# SH9_-_MICROCONTROLLER.net
KiCad netlist of a schematic drawn in Altium Designer
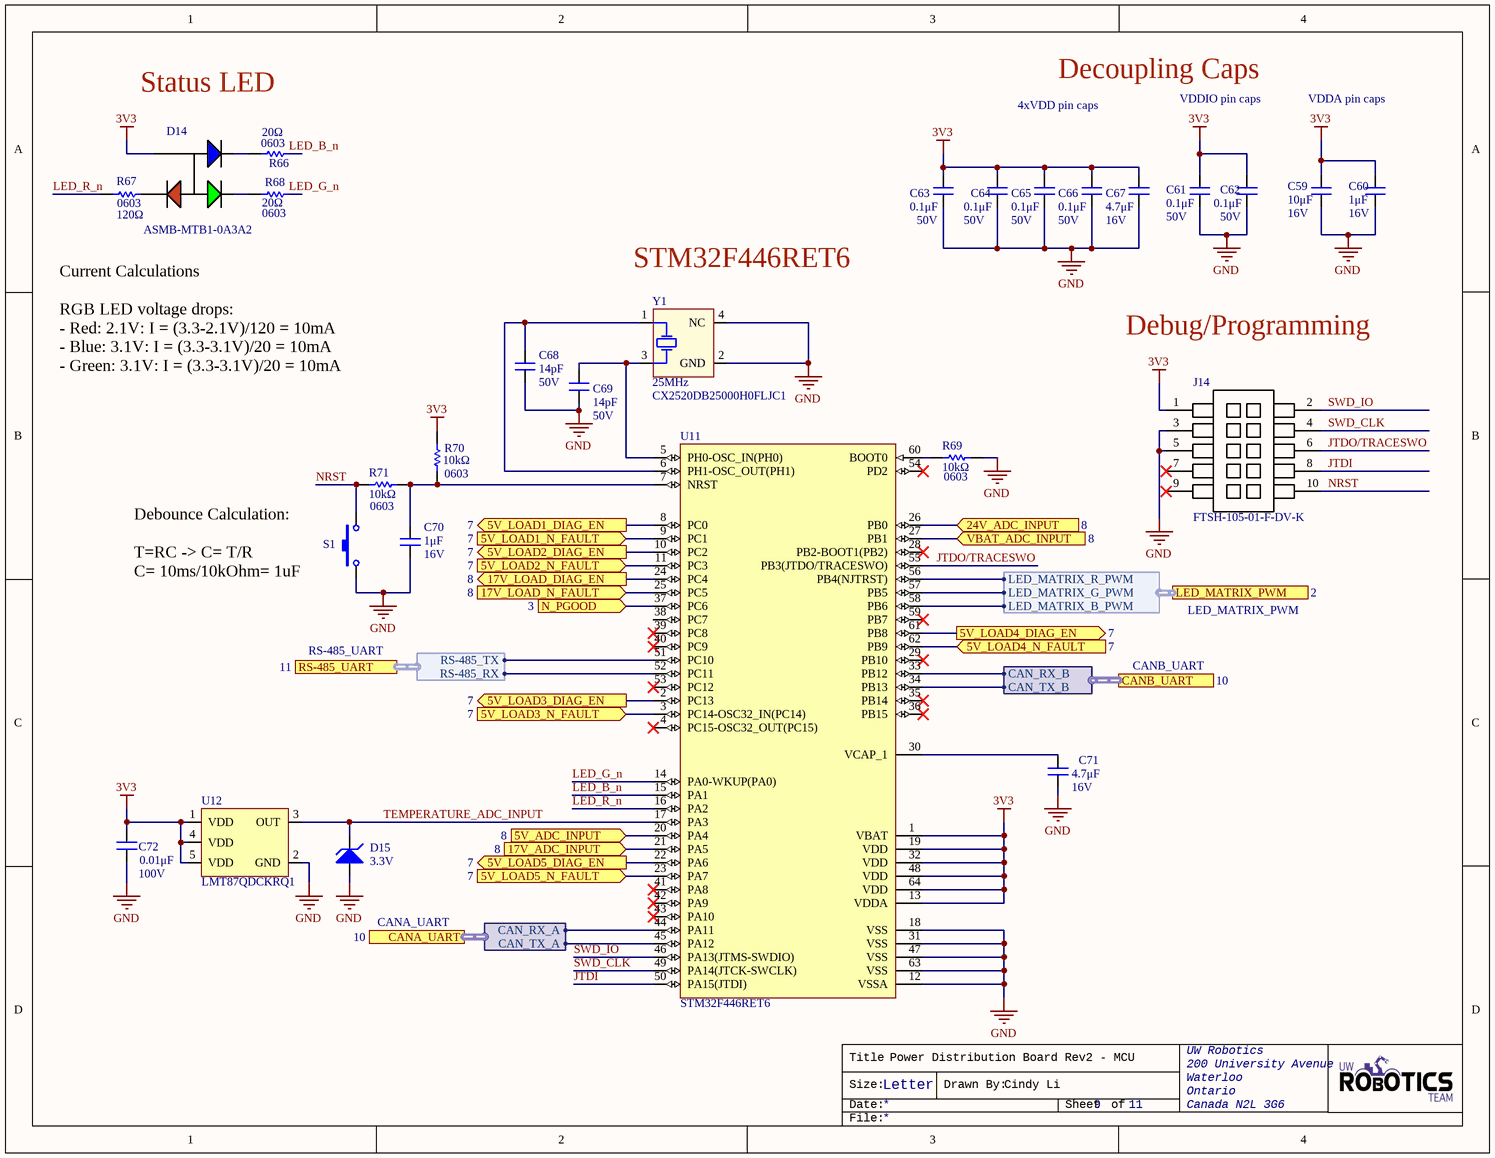
[diagram p0: SH9 - MICROCONTROLLER.SchDoc]

(export (version "E")
  (design (tool "Eeschema 10.0.6"))
  (components
    (comp (ref "C59")
      (value "10μF")
      (footprint "CAP0603")
      (description "CAP CER 10000PF 16V X7R 0603")
      (fields (field (name "VOLTAGE RATING") "16V") (field (name "Comment") "CAP_10nF_0603"))
      (libsource (lib "UWRT_Schematic_Library_2020") (part "CAP_10nF_0603"))
    )
    (comp (ref "C60")
      (value "1μF")
      (footprint "CAP0603")
      (description "CAP CER 1UF 16V Y5V 0603")
      (fields
        (field (name "VOLTAGE RATING") "16V")
        (field (name "MANUFACTURER PART NUMBER") "CC0603ZRY5V7BB105")
        (field (name "Comment") "CAP_1uF_16V_0603")
      )
      (libsource (lib "UWRT_Schematic_Library_2020") (part "CAP_1uF_16V_0603"))
    )
    (comp (ref "C61")
      (value "0.1μF")
      (footprint "CAP0603")
      (description "CAP CER 0.1UF 50V X7R 0603")
      (fields (field (name "VOLTAGE RATING") "50V") (field (name "Comment") "CAP_0.1uF_50V_0603"))
      (libsource (lib "UWRT_Schematic_Library_2020") (part "CAP_0.1uF_50V_0603"))
    )
    (comp (ref "C62")
      (value "0.1μF")
      (footprint "CAP0603")
      (description "CAP CER 0.1UF 50V X7R 0603")
      (fields (field (name "VOLTAGE RATING") "50V") (field (name "Comment") "CAP_0.1uF_50V_0603"))
      (libsource (lib "UWRT_Schematic_Library_2020") (part "CAP_0.1uF_50V_0603"))
    )
    (comp (ref "C63")
      (value "0.1μF")
      (footprint "CAP0603")
      (description "CAP CER 0.1UF 50V X7R 0603")
      (fields (field (name "VOLTAGE RATING") "50V") (field (name "Comment") "CAP_0.1uF_50V_0603"))
      (libsource (lib "UWRT_Schematic_Library_2020") (part "CAP_0.1uF_50V_0603"))
    )
    (comp (ref "C64")
      (value "0.1μF")
      (footprint "CAP0603")
      (description "CAP CER 0.1UF 50V X7R 0603")
      (fields (field (name "VOLTAGE RATING") "50V") (field (name "Comment") "CAP_0.1uF_50V_0603"))
      (libsource (lib "UWRT_Schematic_Library_2020") (part "CAP_0.1uF_50V_0603"))
    )
    (comp (ref "C65")
      (value "0.1μF")
      (footprint "CAP0603")
      (description "CAP CER 0.1UF 50V X7R 0603")
      (fields (field (name "VOLTAGE RATING") "50V") (field (name "Comment") "CAP_0.1uF_50V_0603"))
      (libsource (lib "UWRT_Schematic_Library_2020") (part "CAP_0.1uF_50V_0603"))
    )
    (comp (ref "C66")
      (value "0.1μF")
      (footprint "CAP0603")
      (description "CAP CER 0.1UF 50V X7R 0603")
      (fields (field (name "VOLTAGE RATING") "50V") (field (name "Comment") "CAP_0.1uF_50V_0603"))
      (libsource (lib "UWRT_Schematic_Library_2020") (part "CAP_0.1uF_50V_0603"))
    )
    (comp (ref "C67")
      (value "4.7μF")
      (footprint "CAP2012")
      (description "CAP CER 4.7UF 16V X5R 0805")
      (fields
        (field (name "VOLTAGE RATING") "16V")
        (field (name "TOLERANCE") "10%")
        (field (name "Comment") "CAP_4.7uF_16V_0805")
      )
      (libsource (lib "UWRT_Schematic_Library_2020") (part "CAP_4.7uF_16V_0805"))
    )
    (comp (ref "C68")
      (value "14pF")
      (footprint "CAP0603")
      (description "CAP CER 14PF 50V C0G/NP0 0603")
      (fields
        (field (name "TOLERANCE") "5%")
        (field (name "VOLTAGE RATING") "50V")
        (field (name "Comment") "CAP_14pF_50V_0603")
      )
      (libsource (lib "UWRT_Schematic_Library_2020") (part "CAP_14pF_50V_0603"))
    )
    (comp (ref "C69")
      (value "14pF")
      (footprint "CAP0603")
      (description "CAP CER 14PF 50V C0G/NP0 0603")
      (fields
        (field (name "TOLERANCE") "5%")
        (field (name "VOLTAGE RATING") "50V")
        (field (name "Comment") "CAP_14pF_50V_0603")
      )
      (libsource (lib "UWRT_Schematic_Library_2020") (part "CAP_14pF_50V_0603"))
    )
    (comp (ref "C70")
      (value "1μF")
      (footprint "CAP2012")
      (description "CAP CER 1UF 16V X7R 0805")
      (fields
        (field (name "TOLERANCE") "10%")
        (field (name "VOLTAGE RATING") "16V")
        (field (name "Comment") "CAP_1uF_16V_0805")
      )
      (libsource (lib "UWRT_Schematic_Library_2020") (part "CAP_1uF_16V_0805"))
    )
    (comp (ref "C71")
      (value "4.7μF")
      (footprint "CAP2012")
      (description "CAP CER 4.7UF 16V X5R 0805")
      (fields
        (field (name "VOLTAGE RATING") "16V")
        (field (name "TOLERANCE") "10%")
        (field (name "Comment") "CAP_4.7uF_16V_0805")
      )
      (libsource (lib "UWRT_Schematic_Library_2020") (part "CAP_4.7uF_16V_0805"))
    )
    (comp (ref "C72")
      (value "0.01μF")
      (footprint "CAP0603")
      (description "CAP CER 10000PF 100V X7R 0603")
      (fields (field (name "VOLTAGE RATING") "100V") (field (name "Comment") "CAP_0.01uF_100V_0603"))
      (libsource (lib "UWRT_Schematic_Library_2020") (part "CAP_0.01uF_100V_0603"))
    )
    (comp (ref "D14")
      (value "LED_RGB")
      (footprint "LED_RGB")
      (description "LED RGB DIFFUSED 4PLCC SMD")
      (fields (field (name "MANUFACTURER PART NUMBER 1") "ASMB-MTB1-0A3A2"))
      (libsource (lib "UWRT_Schematic_Library_2020") (part "LED_RGB"))
    )
    (comp (ref "D15")
      (value "ESD5Z3.3T1G")
      (footprint "SOD523_UNI")
      (description "ESD5Z3.3T1G,SOD523 ESD DIODE < AZ")
      (fields (field (name "REVERSE STANDOFF VOLTAGE") "3.3V"))
      (libsource (lib "UWRT_Schematic_Library_2020") (part "ESD5Z3.3T1G"))
    )
    (comp (ref "J14")
      (value "CON_PROGRAMMING")
      (footprint "FTSH-105-01-F-DV-K-P-TR")
      (fields (field (name "MANUFACTURER PART NUMBER 1") "FTSH-105-01-F-DV-K"))
      (libsource (lib "UWRT_Schematic_Library_2020") (part "CON_PROGRAMMING"))
    )
    (comp (ref "R66")
      (value "20Ω")
      (footprint "RESC0603(1608)_N")
      (description "RES SMD 20 OHM 5% 1/10W 0603")
      (fields
        (field (name "TOLERANCE") "5%")
        (field (name "CASE CODE (IMPERIAL)") "0603")
        (field (name "Comment") "RES_20Ω_0603")
      )
      (libsource (lib "UWRT_Schematic_Library_2020") (part "RES_20Ω_0603"))
    )
    (comp (ref "R67")
      (value "120Ω")
      (footprint "RESC0603(1608)_N")
      (description "RES SMD 120 OHM 5% 1/10W 0603")
      (fields
        (field (name "TOLERANCE") "5%")
        (field (name "CASE CODE (IMPERIAL)") "0603")
        (field (name "Comment") "RES_120Ω_0603")
      )
      (libsource (lib "UWRT_Schematic_Library_2020") (part "RES_120Ω_0603"))
    )
    (comp (ref "R68")
      (value "20Ω")
      (footprint "RESC0603(1608)_N")
      (description "RES SMD 20 OHM 5% 1/10W 0603")
      (fields
        (field (name "TOLERANCE") "5%")
        (field (name "CASE CODE (IMPERIAL)") "0603")
        (field (name "Comment") "RES_20Ω_0603")
      )
      (libsource (lib "UWRT_Schematic_Library_2020") (part "RES_20Ω_0603"))
    )
    (comp (ref "R69")
      (value "10kΩ")
      (footprint "RESC0603(1608)_N")
      (description "RES SMD 10K OHM 5% 1/10W 0603")
      (fields
        (field (name "TOLERANCE") "5%")
        (field (name "CASE CODE (IMPERIAL)") "0603")
        (field (name "Comment") "RES_10kΩ_0603")
      )
      (libsource (lib "UWRT_Schematic_Library_2020") (part "RES_10kΩ_0603"))
    )
    (comp (ref "R70")
      (value "10kΩ")
      (footprint "RESC0603(1608)_N")
      (description "RES SMD 10K OHM 5% 1/10W 0603")
      (fields
        (field (name "TOLERANCE") "5%")
        (field (name "CASE CODE (IMPERIAL)") "0603")
        (field (name "Comment") "RES_10kΩ_0603")
      )
      (libsource (lib "UWRT_Schematic_Library_2020") (part "RES_10kΩ_0603"))
    )
    (comp (ref "R71")
      (value "10kΩ")
      (footprint "RESC0603(1608)_N")
      (description "RES 10K OHM 5% 1/10W 0603")
      (fields
        (field (name "TOLERANCE") "5%")
        (field (name "CASE CODE (IMPERIAL)") "0603")
        (field (name "Comment") "RES_10kΩ_0603")
      )
      (libsource (lib "UWRT_Schematic_Library_2020") (part "RES_10kΩ_0603_5%"))
    )
    (comp (ref "S1")
      (value "SW_TACTILE")
      (footprint "B3U-1000P")
      (description "Tactile Switch (Grey)")
      (libsource (lib "UWRT_Schematic_Library_2020") (part "SW_TACTILE"))
    )
    (comp (ref "U11")
      (value "STM32F446RET6")
      (footprint "STM-LQFP64_L")
      (libsource (lib "UWRT_Schematic_Library_2020") (part "MCU_STM32F446RET6"))
    )
    (comp (ref "U12")
      (value "IC TEMPERATURE_SENSOR")
      (footprint "SOT65P210X110-5N")
      (description "SENSOR ANALOG -50C-150C SC70")
      (fields (field (name "MANUFACTURER PART NUMBER 1") "LMT87QDCKRQ1"))
      (libsource (lib "UWRT_Schematic_Library_2020") (part "IC TEMPERATURE_SENSOR"))
    )
    (comp (ref "Y1")
      (value "CRYSTAL_25MHZ")
      (footprint "SOIC254P1016X440-4N")
      (description "CRYSTAL 25.0000MHZ 12PF SMD")
      (fields
        (field (name "FREQUENCY") "25MHz")
        (field (name "MANUFACTURER PART NUMBER 1") "CX2520DB25000H0FLJC1")
      )
      (libsource (lib "UWRT_Schematic_Library_2020") (part "CRYSTAL_25MHZ"))
    )
  )
  (nets
    (net (code "5") (name "/5V_ADC_INPUT") (class "Default")
      (node (ref "U11") (pin "20") (pinfunction "PA4_20") (pintype "bidirectional"))
    )
    (net (code "6") (name "/5V_LOAD1_DIAG_EN") (class "Default")
      (node (ref "U11") (pin "8") (pinfunction "PC0_8") (pintype "bidirectional"))
    )
    (net (code "7") (name "/5V_LOAD1_N_FAULT") (class "Default")
      (node (ref "U11") (pin "9") (pinfunction "PC1_9") (pintype "bidirectional"))
    )
    (net (code "8") (name "/5V_LOAD2_DIAG_EN") (class "Default")
      (node (ref "U11") (pin "10") (pinfunction "PC2_10") (pintype "bidirectional"))
    )
    (net (code "9") (name "/5V_LOAD2_N_FAULT") (class "Default")
      (node (ref "U11") (pin "11") (pinfunction "PC3_11") (pintype "bidirectional"))
    )
    (net (code "10") (name "/5V_LOAD3_DIAG_EN") (class "Default")
      (node (ref "U11") (pin "2") (pinfunction "PC13_2") (pintype "bidirectional"))
    )
    (net (code "11") (name "/5V_LOAD3_N_FAULT") (class "Default")
      (node (ref "U11") (pin "3") (pinfunction "PC14-OSC32_IN(PC14)_3") (pintype "bidirectional"))
    )
    (net (code "12") (name "/5V_LOAD4_DIAG_EN") (class "Default")
      (node (ref "U11") (pin "61") (pinfunction "PB8_61") (pintype "bidirectional"))
    )
    (net (code "13") (name "/5V_LOAD4_N_FAULT") (class "Default")
      (node (ref "U11") (pin "62") (pinfunction "PB9_62") (pintype "bidirectional"))
    )
    (net (code "14") (name "/5V_LOAD5_DIAG_EN") (class "Default")
      (node (ref "U11") (pin "22") (pinfunction "PA6_22") (pintype "bidirectional"))
    )
    (net (code "15") (name "/5V_LOAD5_N_FAULT") (class "Default")
      (node (ref "U11") (pin "23") (pinfunction "PA7_23") (pintype "bidirectional"))
    )
    (net (code "16") (name "/17V_ADC_INPUT") (class "Default")
      (node (ref "U11") (pin "21") (pinfunction "PA5_21") (pintype "bidirectional"))
    )
    (net (code "17") (name "/17V_LOAD_DIAG_EN") (class "Default")
      (node (ref "U11") (pin "24") (pinfunction "PC4_24") (pintype "bidirectional"))
    )
    (net (code "18") (name "/17V_LOAD_N_FAULT") (class "Default")
      (node (ref "U11") (pin "25") (pinfunction "PC5_25") (pintype "bidirectional"))
    )
    (net (code "19") (name "/24V_ADC_INPUT") (class "Default")
      (node (ref "U11") (pin "26") (pinfunction "PB0_26") (pintype "bidirectional"))
    )
    (net (code "20") (name "/CAN_RX_A") (class "Default")
      (node (ref "U11") (pin "44") (pinfunction "PA11_44") (pintype "bidirectional"))
    )
    (net (code "21") (name "/CAN_RX_B") (class "Default")
      (node (ref "U11") (pin "33") (pinfunction "PB12_33") (pintype "bidirectional"))
    )
    (net (code "22") (name "/CAN_TX_A") (class "Default")
      (node (ref "U11") (pin "45") (pinfunction "PA12_45") (pintype "bidirectional"))
    )
    (net (code "23") (name "/CAN_TX_B") (class "Default")
      (node (ref "U11") (pin "34") (pinfunction "PB13_34") (pintype "bidirectional"))
    )
    (net (code "24") (name "/JTDI") (class "Default")
      (node (ref "J14") (pin "8") (pinfunction "8_8") (pintype "passive"))
      (node (ref "U11") (pin "50") (pinfunction "PA15(JTDI)_50") (pintype "bidirectional"))
    )
    (net (code "25") (name "/JTDO{slash}TRACESWO") (class "Default")
      (node (ref "J14") (pin "6") (pinfunction "6_6") (pintype "passive"))
      (node (ref "U11") (pin "55") (pinfunction "PB3(JTDO/TRACESWO)_55") (pintype "bidirectional"))
    )
    (net (code "26") (name "/LED_B_n") (class "Default")
      (node (ref "R66") (pin "2") (pinfunction "2_2") (pintype "passive"))
      (node (ref "U11") (pin "15") (pinfunction "PA1_15") (pintype "bidirectional"))
    )
    (net (code "27") (name "/LED_G_n") (class "Default")
      (node (ref "R68") (pin "2") (pinfunction "2_2") (pintype "passive"))
      (node (ref "U11") (pin "14") (pinfunction "PA0-WKUP(PA0)_14") (pintype "bidirectional"))
    )
    (net (code "28") (name "/LED_MATRIX_B_PWM") (class "Default")
      (node (ref "U11") (pin "58") (pinfunction "PB6_58") (pintype "bidirectional"))
    )
    (net (code "29") (name "/LED_MATRIX_G_PWM") (class "Default")
      (node (ref "U11") (pin "57") (pinfunction "PB5_57") (pintype "bidirectional"))
    )
    (net (code "30") (name "/LED_MATRIX_R_PWM") (class "Default")
      (node (ref "U11") (pin "56") (pinfunction "PB4(NJTRST)_56") (pintype "bidirectional"))
    )
    (net (code "31") (name "/LED_R_n") (class "Default")
      (node (ref "R67") (pin "1") (pinfunction "1_1") (pintype "passive"))
      (node (ref "U11") (pin "16") (pinfunction "PA2_16") (pintype "bidirectional"))
    )
    (net (code "32") (name "/NRST") (class "Default")
      (node (ref "J14") (pin "10") (pinfunction "10_10") (pintype "passive"))
      (node (ref "R71") (pin "2") (pinfunction "2_2") (pintype "passive"))
      (node (ref "S1") (pin "2") (pinfunction "2_2") (pintype "passive"))
    )
    (net (code "33") (name "/N_PGOOD") (class "Default")
      (node (ref "U11") (pin "37") (pinfunction "PC6_37") (pintype "bidirectional"))
    )
    (net (code "34") (name "/RS-485_RX") (class "Default")
      (node (ref "U11") (pin "52") (pinfunction "PC11_52") (pintype "bidirectional"))
    )
    (net (code "35") (name "/RS-485_TX") (class "Default")
      (node (ref "U11") (pin "51") (pinfunction "PC10_51") (pintype "bidirectional"))
    )
    (net (code "36") (name "/SWD_CLK") (class "Default")
      (node (ref "J14") (pin "4") (pinfunction "4_4") (pintype "passive"))
      (node (ref "U11") (pin "49") (pinfunction "PA14(JTCK-SWCLK)_49") (pintype "bidirectional"))
    )
    (net (code "37") (name "/SWD_IO") (class "Default")
      (node (ref "J14") (pin "2") (pinfunction "2_2") (pintype "passive"))
      (node (ref "U11") (pin "46") (pinfunction "PA13(JTMS-SWDIO)_46") (pintype "bidirectional"))
    )
    (net (code "38") (name "/TEMPERATURE_ADC_INPUT") (class "Default")
      (node (ref "D15") (pin "2") (pinfunction "2_2") (pintype "passive"))
      (node (ref "U11") (pin "17") (pinfunction "PA3_17") (pintype "bidirectional"))
      (node (ref "U12") (pin "3") (pinfunction "OUT_3") (pintype "passive"))
    )
    (net (code "39") (name "/VBAT_ADC_INPUT") (class "Default")
      (node (ref "U11") (pin "27") (pinfunction "PB1_27") (pintype "bidirectional"))
    )
    (net (code "44") (name "3V3") (class "Default")
      (node (ref "C59") (pin "2") (pinfunction "2_2") (pintype "passive"))
      (node (ref "C60") (pin "2") (pinfunction "2_2") (pintype "passive"))
      (node (ref "C61") (pin "2") (pinfunction "2_2") (pintype "passive"))
      (node (ref "C62") (pin "2") (pinfunction "2_2") (pintype "passive"))
      (node (ref "C63") (pin "2") (pinfunction "2_2") (pintype "passive"))
      (node (ref "C64") (pin "2") (pinfunction "2_2") (pintype "passive"))
      (node (ref "C65") (pin "2") (pinfunction "2_2") (pintype "passive"))
      (node (ref "C66") (pin "2") (pinfunction "2_2") (pintype "passive"))
      (node (ref "C67") (pin "2") (pinfunction "2_2") (pintype "passive"))
      (node (ref "C72") (pin "2") (pinfunction "2_2") (pintype "passive"))
      (node (ref "D14") (pin "4") (pinfunction "COMMON_ANODE_4") (pintype "passive"))
      (node (ref "J14") (pin "1") (pinfunction "1_1") (pintype "passive"))
      (node (ref "R70") (pin "2") (pinfunction "2_2") (pintype "passive"))
      (node (ref "U11") (pin "1") (pinfunction "VBAT_1") (pintype "power_in"))
      (node (ref "U11") (pin "13") (pinfunction "VDDA_13") (pintype "power_in"))
      (node (ref "U11") (pin "19") (pinfunction "VDD_19") (pintype "power_in"))
      (node (ref "U11") (pin "32") (pinfunction "VDD_32") (pintype "power_in"))
      (node (ref "U11") (pin "48") (pinfunction "VDD_48") (pintype "power_in"))
      (node (ref "U11") (pin "64") (pinfunction "VDD_64") (pintype "power_in"))
      (node (ref "U12") (pin "1") (pinfunction "VDD_1") (pintype "passive"))
      (node (ref "U12") (pin "4") (pinfunction "VDD_4") (pintype "passive"))
      (node (ref "U12") (pin "5") (pinfunction "VDD_5") (pintype "passive"))
    )
    (net (code "45") (name "GND") (class "Default")
      (node (ref "C59") (pin "1") (pinfunction "1_1") (pintype "passive"))
      (node (ref "C60") (pin "1") (pinfunction "1_1") (pintype "passive"))
      (node (ref "C61") (pin "1") (pinfunction "1_1") (pintype "passive"))
      (node (ref "C62") (pin "1") (pinfunction "1_1") (pintype "passive"))
      (node (ref "C63") (pin "1") (pinfunction "1_1") (pintype "passive"))
      (node (ref "C64") (pin "1") (pinfunction "1_1") (pintype "passive"))
      (node (ref "C65") (pin "1") (pinfunction "1_1") (pintype "passive"))
      (node (ref "C66") (pin "1") (pinfunction "1_1") (pintype "passive"))
      (node (ref "C67") (pin "1") (pinfunction "1_1") (pintype "passive"))
      (node (ref "C68") (pin "1") (pinfunction "1_1") (pintype "passive"))
      (node (ref "C69") (pin "1") (pinfunction "1_1") (pintype "passive"))
      (node (ref "C70") (pin "1") (pinfunction "1_1") (pintype "passive"))
      (node (ref "C71") (pin "1") (pinfunction "1_1") (pintype "passive"))
      (node (ref "C72") (pin "1") (pinfunction "1_1") (pintype "passive"))
      (node (ref "D15") (pin "1") (pinfunction "1_1") (pintype "passive"))
      (node (ref "J14") (pin "3") (pinfunction "3_3") (pintype "passive"))
      (node (ref "J14") (pin "5") (pinfunction "5_5") (pintype "passive"))
      (node (ref "R69") (pin "2") (pinfunction "2_2") (pintype "passive"))
      (node (ref "S1") (pin "1") (pinfunction "1_1") (pintype "passive"))
      (node (ref "U11") (pin "12") (pinfunction "VSSA_12") (pintype "power_in"))
      (node (ref "U11") (pin "18") (pinfunction "VSS_18") (pintype "power_in"))
      (node (ref "U11") (pin "31") (pinfunction "VSS_31") (pintype "power_in"))
      (node (ref "U11") (pin "47") (pinfunction "VSS_47") (pintype "power_in"))
      (node (ref "U11") (pin "63") (pinfunction "VSS_63") (pintype "power_in"))
      (node (ref "U12") (pin "2") (pinfunction "GND_2") (pintype "passive"))
      (node (ref "Y1") (pin "2") (pinfunction "GND_2") (pintype "power_in"))
      (node (ref "Y1") (pin "4") (pinfunction "NC_4") (pintype "passive"))
    )
    (net (code "46") (name "Net-(D14-CATHODE_(BLUE))") (class "Default")
      (node (ref "D14") (pin "3") (pinfunction "CATHODE_(BLUE)_3") (pintype "passive"))
      (node (ref "R66") (pin "1") (pinfunction "1_1") (pintype "passive"))
    )
    (net (code "47") (name "Net-(D14-CATHODE_(GREEN))") (class "Default")
      (node (ref "D14") (pin "2") (pinfunction "CATHODE_(GREEN)_2") (pintype "passive"))
      (node (ref "R68") (pin "1") (pinfunction "1_1") (pintype "passive"))
    )
    (net (code "48") (name "Net-(D14-CATHODE_(RED))") (class "Default")
      (node (ref "D14") (pin "1") (pinfunction "CATHODE_(RED)_1") (pintype "passive"))
      (node (ref "R67") (pin "2") (pinfunction "2_2") (pintype "passive"))
    )
    (net (code "49") (name "Net-(U11-BOOT0)") (class "Default")
      (node (ref "R69") (pin "1") (pinfunction "1_1") (pintype "passive"))
      (node (ref "U11") (pin "60") (pinfunction "BOOT0_60") (pintype "input"))
    )
    (net (code "50") (name "Net-(U11-NRST)") (class "Default")
      (node (ref "C70") (pin "2") (pinfunction "2_2") (pintype "passive"))
      (node (ref "R70") (pin "1") (pinfunction "1_1") (pintype "passive"))
      (node (ref "R71") (pin "1") (pinfunction "1_1") (pintype "passive"))
      (node (ref "U11") (pin "7") (pinfunction "NRST_7") (pintype "bidirectional"))
    )
    (net (code "51") (name "Net-(U11-PH0-OSC_IN(PH0))") (class "Default")
      (node (ref "C69") (pin "2") (pinfunction "2_2") (pintype "passive"))
      (node (ref "U11") (pin "5") (pinfunction "PH0-OSC_IN(PH0)_5") (pintype "bidirectional"))
      (node (ref "Y1") (pin "3") (pinfunction "HOT_3") (pintype "passive"))
    )
    (net (code "52") (name "Net-(U11-PH1-OSC_OUT(PH1))") (class "Default")
      (node (ref "C68") (pin "2") (pinfunction "2_2") (pintype "passive"))
      (node (ref "U11") (pin "6") (pinfunction "PH1-OSC_OUT(PH1)_6") (pintype "bidirectional"))
      (node (ref "Y1") (pin "1") (pinfunction "HOT_1") (pintype "passive"))
    )
    (net (code "53") (name "Net-(U11-VCAP_1)") (class "Default")
      (node (ref "C71") (pin "2") (pinfunction "2_2") (pintype "passive"))
      (node (ref "U11") (pin "30") (pinfunction "VCAP_1_30") (pintype "passive"))
    )
    (net (code "54") (name "unconnected-(J14-Pad7)") (class "Default")
      (node (ref "J14") (pin "7") (pinfunction "7_7") (pintype "passive+no_connect"))
    )
    (net (code "55") (name "unconnected-(J14-Pad9)") (class "Default")
      (node (ref "J14") (pin "9") (pinfunction "9_9") (pintype "passive+no_connect"))
    )
    (net (code "56") (name "unconnected-(U11-PA8-Pad41)") (class "Default")
      (node (ref "U11") (pin "41") (pinfunction "PA8_41") (pintype "bidirectional+no_connect"))
    )
    (net (code "57") (name "unconnected-(U11-PA9-Pad42)") (class "Default")
      (node (ref "U11") (pin "42") (pinfunction "PA9_42") (pintype "bidirectional+no_connect"))
    )
    (net (code "58") (name "unconnected-(U11-PA10-Pad43)") (class "Default")
      (node (ref "U11") (pin "43") (pinfunction "PA10_43") (pintype "bidirectional+no_connect"))
    )
    (net (code "59") (name "unconnected-(U11-PB2-BOOT1(PB2)-Pad28)") (class "Default")
      (node (ref "U11") (pin "28") (pinfunction "PB2-BOOT1(PB2)_28") (pintype "bidirectional+no_connect"))
    )
    (net (code "60") (name "unconnected-(U11-PB7-Pad59)") (class "Default")
      (node (ref "U11") (pin "59") (pinfunction "PB7_59") (pintype "bidirectional+no_connect"))
    )
    (net (code "61") (name "unconnected-(U11-PB10-Pad29)") (class "Default")
      (node (ref "U11") (pin "29") (pinfunction "PB10_29") (pintype "bidirectional+no_connect"))
    )
    (net (code "62") (name "unconnected-(U11-PB14-Pad35)") (class "Default")
      (node (ref "U11") (pin "35") (pinfunction "PB14_35") (pintype "bidirectional+no_connect"))
    )
    (net (code "63") (name "unconnected-(U11-PB15-Pad36)") (class "Default")
      (node (ref "U11") (pin "36") (pinfunction "PB15_36") (pintype "bidirectional+no_connect"))
    )
    (net (code "64") (name "unconnected-(U11-PC7-Pad38)") (class "Default")
      (node (ref "U11") (pin "38") (pinfunction "PC7_38") (pintype "bidirectional"))
    )
    (net (code "65") (name "unconnected-(U11-PC8-Pad39)") (class "Default")
      (node (ref "U11") (pin "39") (pinfunction "PC8_39") (pintype "bidirectional+no_connect"))
    )
    (net (code "66") (name "unconnected-(U11-PC9-Pad40)") (class "Default")
      (node (ref "U11") (pin "40") (pinfunction "PC9_40") (pintype "bidirectional+no_connect"))
    )
    (net (code "67") (name "unconnected-(U11-PC12-Pad53)") (class "Default")
      (node (ref "U11") (pin "53") (pinfunction "PC12_53") (pintype "bidirectional+no_connect"))
    )
    (net (code "68") (name "unconnected-(U11-PC15-OSC32_OUT(PC15)-Pad4)") (class "Default")
      (node (ref "U11") (pin "4") (pinfunction "PC15-OSC32_OUT(PC15)_4") (pintype "bidirectional+no_connect"))
    )
    (net (code "69") (name "unconnected-(U11-PD2-Pad54)") (class "Default")
      (node (ref "U11") (pin "54") (pinfunction "PD2_54") (pintype "bidirectional+no_connect"))
    )
  )
)
